# ArduinoShield_SFE_2x16LCD_RGB.net
KiCad netlist of a schematic drawn in EAGLE
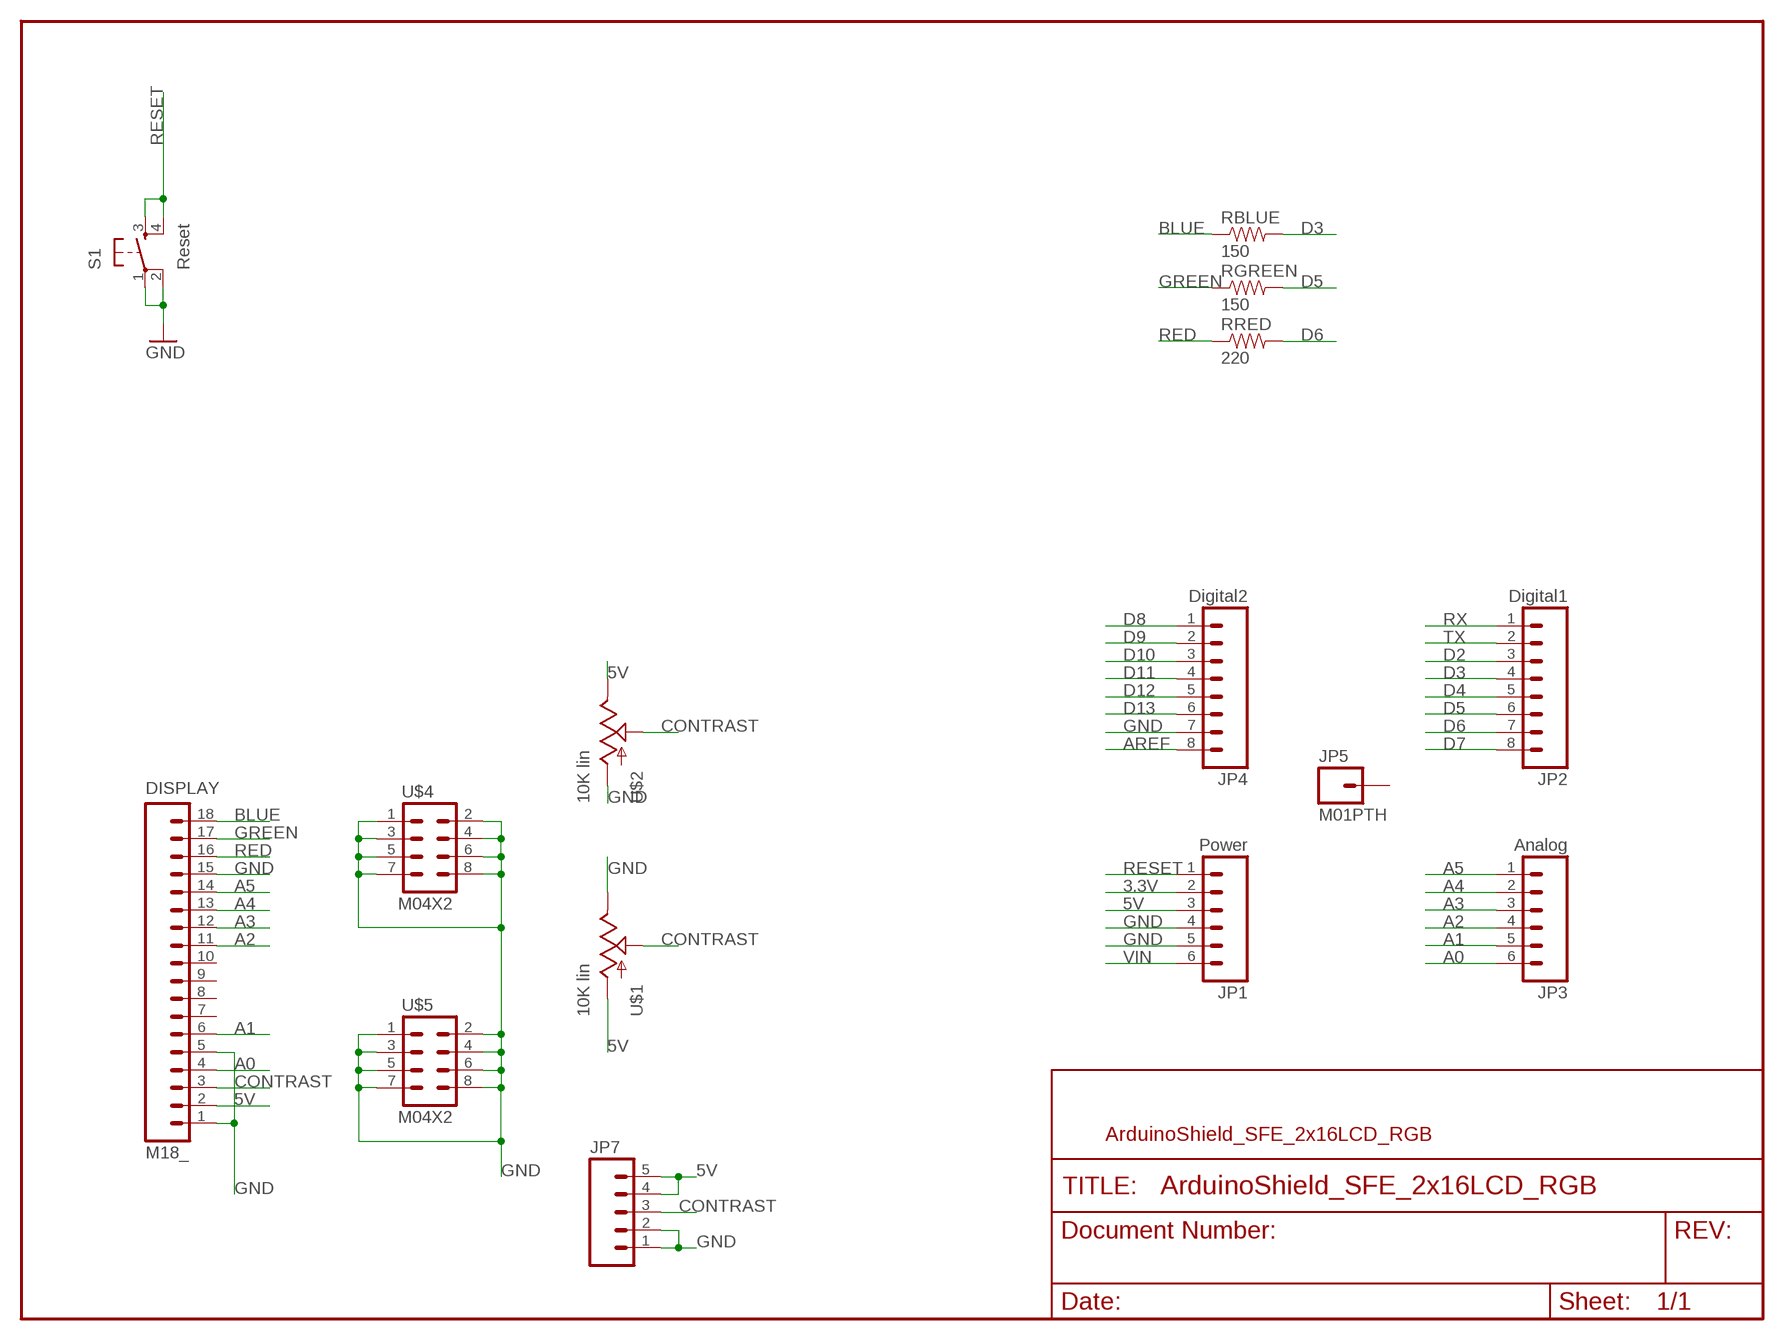
[diagram p0: schematic, sheet 1]

(export (version "E")
  (design (tool "Eeschema 10.0.6"))
  (components
    (comp (ref "DISPLAY")
      (value "M18_")
      (footprint "eagle-import:1X18")
      (libsource (lib "eagle-import") (part "M18_"))
    )
    (comp (ref "JP1")
      (value "Power")
      (footprint "eagle-import:1X06")
      (libsource (lib "eagle-import") (part "M06SIP"))
    )
    (comp (ref "JP2")
      (value "Digital1")
      (footprint "eagle-import:1X08")
      (libsource (lib "eagle-import") (part "M08"))
    )
    (comp (ref "JP3")
      (value "Analog")
      (footprint "eagle-import:1X06")
      (libsource (lib "eagle-import") (part "M06SIP"))
    )
    (comp (ref "JP4")
      (value "Digital2")
      (footprint "eagle-import:1X08")
      (libsource (lib "eagle-import") (part "M08"))
    )
    (comp (ref "JP5")
      (value "M01PTH")
      (footprint "eagle-import:1X01")
      (libsource (lib "eagle-import") (part "M01PTH"))
    )
    (comp (ref "JP7")
      (value "M05PTH_LONGPADS")
      (footprint "eagle-import:1X05_LONGPADS")
      (libsource (lib "eagle-import") (part "M05PTH_LONGPADS"))
    )
    (comp (ref "RBLUE")
      (value "150")
      (footprint "eagle-import:AXIAL-0.5")
      (libsource (lib "eagle-import") (part "RESISTORPTH-1/2W"))
    )
    (comp (ref "RGREEN")
      (value "150")
      (footprint "eagle-import:AXIAL-0.5")
      (libsource (lib "eagle-import") (part "RESISTORPTH-1/2W"))
    )
    (comp (ref "RRED")
      (value "220")
      (footprint "eagle-import:AXIAL-0.5")
      (libsource (lib "eagle-import") (part "RESISTORPTH-1/2W"))
    )
    (comp (ref "S1")
      (value "Reset")
      (footprint "eagle-import:TACTILE-PTH")
      (libsource (lib "eagle-import") (part "TAC_SWITCHPTH"))
    )
    (comp (ref "U$1")
      (value "10K lin")
      (footprint "eagle-import:ALPS_POT")
      (libsource (lib "eagle-import") (part "POT"))
    )
    (comp (ref "U$2")
      (value "10K lin")
      (footprint "eagle-import:POT_ALPHA_RV16AF-20")
      (libsource (lib "eagle-import") (part "POT-RV16AF-20"))
    )
    (comp (ref "U$4")
      (value "M04X2")
      (footprint "eagle-import:2X4")
      (libsource (lib "eagle-import") (part "M04X2"))
    )
    (comp (ref "U$5")
      (value "M04X2")
      (footprint "eagle-import:2X4")
      (libsource (lib "eagle-import") (part "M04X2"))
    )
  )
  (nets
    (net (code "1") (name "/3.3V") (class "Default")
      (node (ref "JP1") (pin "2") (pinfunction "2_2") (pintype "passive"))
    )
    (net (code "2") (name "/5V") (class "Default")
      (node (ref "DISPLAY") (pin "2") (pinfunction "2_2") (pintype "passive"))
      (node (ref "JP1") (pin "3") (pinfunction "3_3") (pintype "passive"))
      (node (ref "JP7") (pin "4") (pinfunction "4_4") (pintype "passive"))
      (node (ref "JP7") (pin "5") (pinfunction "5_5") (pintype "passive"))
      (node (ref "U$1") (pin "P$3") (pinfunction "A_P$3") (pintype "passive"))
      (node (ref "U$2") (pin "3") (pinfunction "E_3") (pintype "passive"))
    )
    (net (code "3") (name "/A0") (class "Default")
      (node (ref "DISPLAY") (pin "4") (pinfunction "4_4") (pintype "passive"))
      (node (ref "JP3") (pin "6") (pinfunction "6_6") (pintype "passive"))
    )
    (net (code "4") (name "/A1") (class "Default")
      (node (ref "DISPLAY") (pin "6") (pinfunction "6_6") (pintype "passive"))
      (node (ref "JP3") (pin "5") (pinfunction "5_5") (pintype "passive"))
    )
    (net (code "5") (name "/A2") (class "Default")
      (node (ref "DISPLAY") (pin "11") (pinfunction "11_11") (pintype "passive"))
      (node (ref "JP3") (pin "4") (pinfunction "4_4") (pintype "passive"))
    )
    (net (code "6") (name "/A3") (class "Default")
      (node (ref "DISPLAY") (pin "12") (pinfunction "12_12") (pintype "passive"))
      (node (ref "JP3") (pin "3") (pinfunction "3_3") (pintype "passive"))
    )
    (net (code "7") (name "/A4") (class "Default")
      (node (ref "DISPLAY") (pin "13") (pinfunction "13_13") (pintype "passive"))
      (node (ref "JP3") (pin "2") (pinfunction "2_2") (pintype "passive"))
    )
    (net (code "8") (name "/A5") (class "Default")
      (node (ref "DISPLAY") (pin "14") (pinfunction "14_14") (pintype "passive"))
      (node (ref "JP3") (pin "1") (pinfunction "1_1") (pintype "passive"))
    )
    (net (code "9") (name "/AREF") (class "Default")
      (node (ref "JP4") (pin "8") (pinfunction "8_8") (pintype "passive"))
    )
    (net (code "10") (name "/BLUE") (class "Default")
      (node (ref "DISPLAY") (pin "18") (pinfunction "18_18") (pintype "passive"))
      (node (ref "RBLUE") (pin "P$1") (pinfunction "1_P$1") (pintype "passive"))
    )
    (net (code "11") (name "/CONTRAST") (class "Default")
      (node (ref "DISPLAY") (pin "3") (pinfunction "3_3") (pintype "passive"))
      (node (ref "JP7") (pin "3") (pinfunction "3_3") (pintype "passive"))
      (node (ref "U$1") (pin "P$2") (pinfunction "S_P$2") (pintype "passive"))
      (node (ref "U$2") (pin "2") (pinfunction "S_2") (pintype "passive"))
    )
    (net (code "12") (name "/D2") (class "Default")
      (node (ref "JP2") (pin "3") (pinfunction "3_3") (pintype "passive"))
    )
    (net (code "13") (name "/D3") (class "Default")
      (node (ref "JP2") (pin "4") (pinfunction "4_4") (pintype "passive"))
      (node (ref "RBLUE") (pin "P$2") (pinfunction "2_P$2") (pintype "passive"))
    )
    (net (code "14") (name "/D4") (class "Default")
      (node (ref "JP2") (pin "5") (pinfunction "5_5") (pintype "passive"))
    )
    (net (code "15") (name "/D5") (class "Default")
      (node (ref "JP2") (pin "6") (pinfunction "6_6") (pintype "passive"))
      (node (ref "RGREEN") (pin "P$2") (pinfunction "2_P$2") (pintype "passive"))
    )
    (net (code "16") (name "/D6") (class "Default")
      (node (ref "JP2") (pin "7") (pinfunction "7_7") (pintype "passive"))
      (node (ref "RRED") (pin "P$2") (pinfunction "2_P$2") (pintype "passive"))
    )
    (net (code "17") (name "/D7") (class "Default")
      (node (ref "JP2") (pin "8") (pinfunction "8_8") (pintype "passive"))
    )
    (net (code "18") (name "/D8") (class "Default")
      (node (ref "JP4") (pin "1") (pinfunction "1_1") (pintype "passive"))
    )
    (net (code "19") (name "/D9") (class "Default")
      (node (ref "JP4") (pin "2") (pinfunction "2_2") (pintype "passive"))
    )
    (net (code "20") (name "/D10") (class "Default")
      (node (ref "JP4") (pin "3") (pinfunction "3_3") (pintype "passive"))
    )
    (net (code "21") (name "/D11") (class "Default")
      (node (ref "JP4") (pin "4") (pinfunction "4_4") (pintype "passive"))
    )
    (net (code "22") (name "/D12") (class "Default")
      (node (ref "JP4") (pin "5") (pinfunction "5_5") (pintype "passive"))
    )
    (net (code "23") (name "/D13") (class "Default")
      (node (ref "JP4") (pin "6") (pinfunction "6_6") (pintype "passive"))
    )
    (net (code "24") (name "/GREEN") (class "Default")
      (node (ref "DISPLAY") (pin "17") (pinfunction "17_17") (pintype "passive"))
      (node (ref "RGREEN") (pin "P$1") (pinfunction "1_P$1") (pintype "passive"))
    )
    (net (code "25") (name "/RED") (class "Default")
      (node (ref "DISPLAY") (pin "16") (pinfunction "16_16") (pintype "passive"))
      (node (ref "RRED") (pin "P$1") (pinfunction "1_P$1") (pintype "passive"))
    )
    (net (code "26") (name "/RESET") (class "Default")
      (node (ref "JP1") (pin "1") (pinfunction "1_1") (pintype "passive"))
      (node (ref "S1") (pin "3") (pinfunction "3_3") (pintype "passive"))
      (node (ref "S1") (pin "4") (pinfunction "4_4") (pintype "passive"))
    )
    (net (code "27") (name "/RX") (class "Default")
      (node (ref "JP2") (pin "1") (pinfunction "1_1") (pintype "passive"))
    )
    (net (code "28") (name "/TX") (class "Default")
      (node (ref "JP2") (pin "2") (pinfunction "2_2") (pintype "passive"))
    )
    (net (code "29") (name "/VIN") (class "Default")
      (node (ref "JP1") (pin "6") (pinfunction "6_6") (pintype "passive"))
    )
    (net (code "30") (name "GND") (class "Default")
      (node (ref "DISPLAY") (pin "1") (pinfunction "1_1") (pintype "passive"))
      (node (ref "DISPLAY") (pin "15") (pinfunction "15_15") (pintype "passive"))
      (node (ref "DISPLAY") (pin "5") (pinfunction "5_5") (pintype "passive"))
      (node (ref "JP1") (pin "4") (pinfunction "4_4") (pintype "passive"))
      (node (ref "JP1") (pin "5") (pinfunction "5_5") (pintype "passive"))
      (node (ref "JP4") (pin "7") (pinfunction "7_7") (pintype "passive"))
      (node (ref "JP7") (pin "1") (pinfunction "1_1") (pintype "passive"))
      (node (ref "JP7") (pin "2") (pinfunction "2_2") (pintype "passive"))
      (node (ref "S1") (pin "1") (pinfunction "1_1") (pintype "passive"))
      (node (ref "S1") (pin "2") (pinfunction "2_2") (pintype "passive"))
      (node (ref "U$1") (pin "P$1") (pinfunction "E_P$1") (pintype "passive"))
      (node (ref "U$2") (pin "1") (pinfunction "A_1") (pintype "passive"))
      (node (ref "U$4") (pin "1") (pinfunction "1_1") (pintype "passive"))
      (node (ref "U$4") (pin "2") (pinfunction "2_2") (pintype "passive"))
      (node (ref "U$4") (pin "3") (pinfunction "3_3") (pintype "passive"))
      (node (ref "U$4") (pin "4") (pinfunction "4_4") (pintype "passive"))
      (node (ref "U$4") (pin "5") (pinfunction "5_5") (pintype "passive"))
      (node (ref "U$4") (pin "6") (pinfunction "6_6") (pintype "passive"))
      (node (ref "U$4") (pin "7") (pinfunction "7_7") (pintype "passive"))
      (node (ref "U$4") (pin "8") (pinfunction "8_8") (pintype "passive"))
      (node (ref "U$5") (pin "1") (pinfunction "1_1") (pintype "passive"))
      (node (ref "U$5") (pin "2") (pinfunction "2_2") (pintype "passive"))
      (node (ref "U$5") (pin "3") (pinfunction "3_3") (pintype "passive"))
      (node (ref "U$5") (pin "4") (pinfunction "4_4") (pintype "passive"))
      (node (ref "U$5") (pin "5") (pinfunction "5_5") (pintype "passive"))
      (node (ref "U$5") (pin "6") (pinfunction "6_6") (pintype "passive"))
      (node (ref "U$5") (pin "7") (pinfunction "7_7") (pintype "passive"))
      (node (ref "U$5") (pin "8") (pinfunction "8_8") (pintype "passive"))
    )
    (net (code "31") (name "unconnected-(DISPLAY-Pad7)") (class "Default")
      (node (ref "DISPLAY") (pin "7") (pinfunction "7_7") (pintype "passive"))
    )
    (net (code "32") (name "unconnected-(DISPLAY-Pad8)") (class "Default")
      (node (ref "DISPLAY") (pin "8") (pinfunction "8_8") (pintype "passive"))
    )
    (net (code "33") (name "unconnected-(DISPLAY-Pad9)") (class "Default")
      (node (ref "DISPLAY") (pin "9") (pinfunction "9_9") (pintype "passive"))
    )
    (net (code "34") (name "unconnected-(DISPLAY-Pad10)") (class "Default")
      (node (ref "DISPLAY") (pin "10") (pinfunction "10_10") (pintype "passive"))
    )
    (net (code "35") (name "unconnected-(JP5-Pad1)") (class "Default")
      (node (ref "JP5") (pin "1") (pinfunction "1_1") (pintype "passive"))
    )
  )
)
